# button_brightness_esp32.net
KiCad netlist of a schematic drawn in Altium Designer
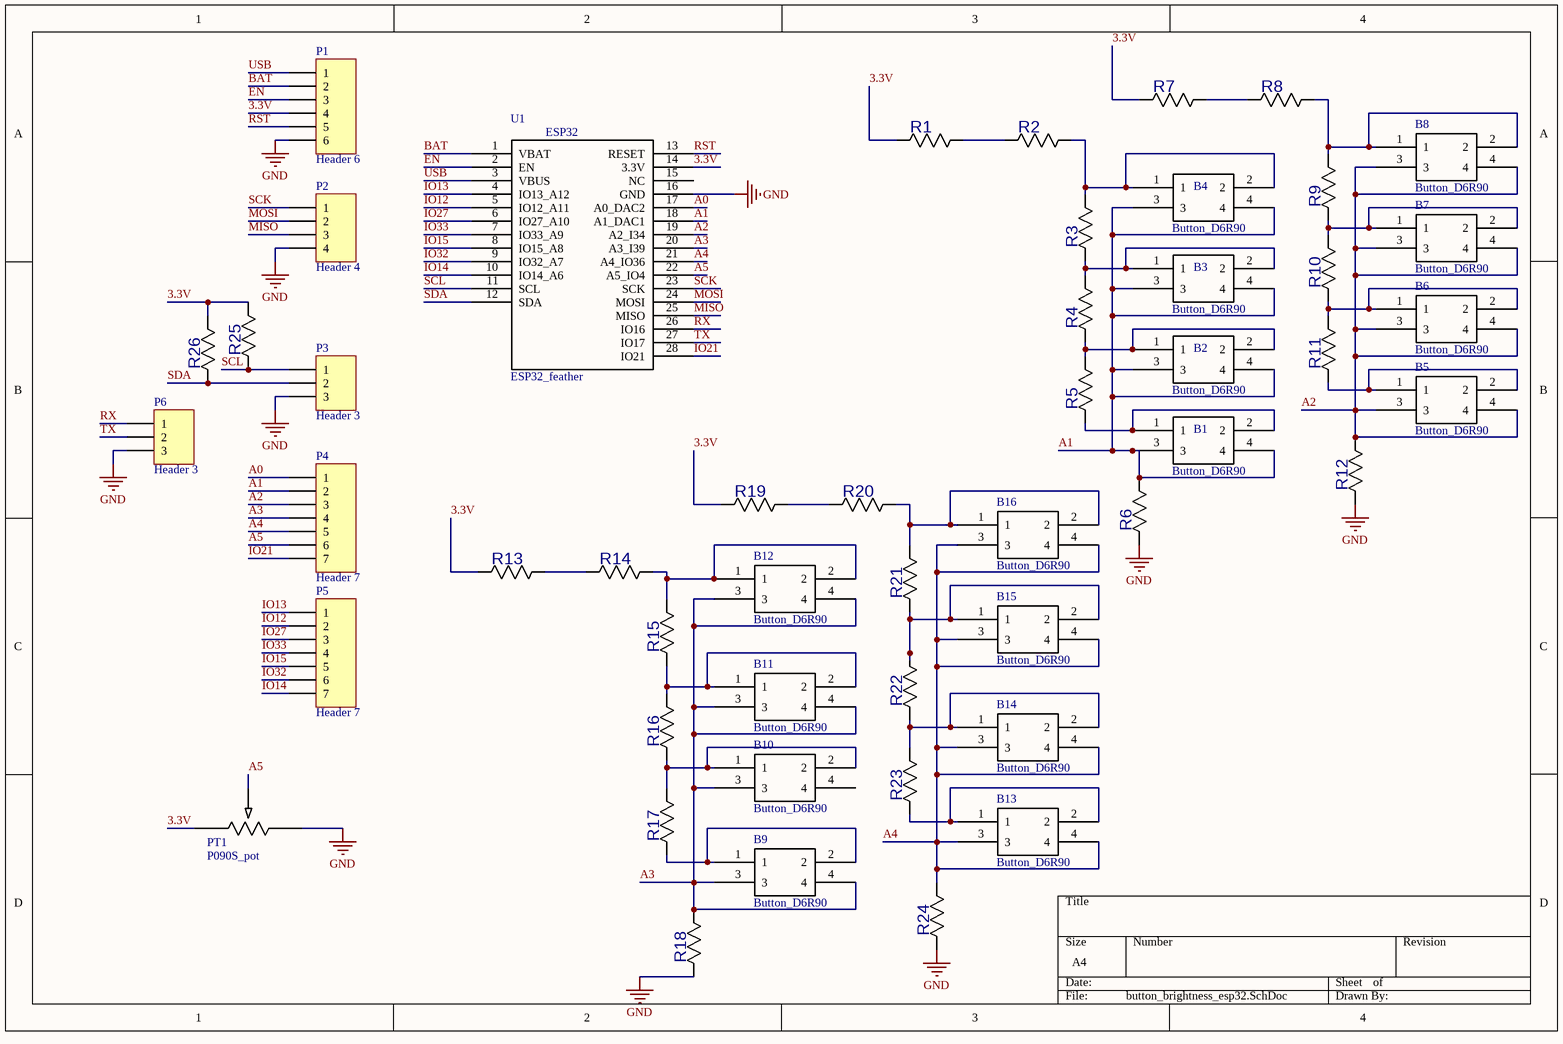
[diagram p0: button_brightness_esp32.SchDoc]

(export (version "E")
  (design (tool "Eeschema 10.0.6"))
  (components
    (comp (ref "B1")
      (value "Button_D6R90")
      (footprint "Button_D6R90")
      (libsource (lib "shematic_lib") (part "Button_D6R90"))
    )
    (comp (ref "B2")
      (value "Button_D6R90")
      (footprint "Button_D6R90")
      (libsource (lib "shematic_lib") (part "Button_D6R90"))
    )
    (comp (ref "B3")
      (value "Button_D6R90")
      (footprint "Button_D6R90")
      (libsource (lib "shematic_lib") (part "Button_D6R90"))
    )
    (comp (ref "B4")
      (value "Button_D6R90")
      (footprint "Button_D6R90")
      (libsource (lib "shematic_lib") (part "Button_D6R90"))
    )
    (comp (ref "B5")
      (value "Button_D6R90")
      (footprint "Button_D6R90")
      (libsource (lib "shematic_lib") (part "Button_D6R90"))
    )
    (comp (ref "B6")
      (value "Button_D6R90")
      (footprint "Button_D6R90")
      (libsource (lib "shematic_lib") (part "Button_D6R90"))
    )
    (comp (ref "B7")
      (value "Button_D6R90")
      (footprint "Button_D6R90")
      (libsource (lib "shematic_lib") (part "Button_D6R90"))
    )
    (comp (ref "B8")
      (value "Button_D6R90")
      (footprint "Button_D6R90")
      (libsource (lib "shematic_lib") (part "Button_D6R90"))
    )
    (comp (ref "B9")
      (value "Button_D6R90")
      (footprint "Button_D6R90")
      (libsource (lib "shematic_lib") (part "Button_D6R90"))
    )
    (comp (ref "B10")
      (value "Button_D6R90")
      (footprint "Button_D6R90")
      (libsource (lib "shematic_lib") (part "Button_D6R90"))
    )
    (comp (ref "B11")
      (value "Button_D6R90")
      (footprint "Button_D6R90")
      (libsource (lib "shematic_lib") (part "Button_D6R90"))
    )
    (comp (ref "B12")
      (value "Button_D6R90")
      (footprint "component_lib:Button_D6R90")
      (libsource (lib "shematic_lib") (part "Button_D6R90"))
    )
    (comp (ref "B13")
      (value "Button_D6R90")
      (footprint "Button_D6R90")
      (libsource (lib "shematic_lib") (part "Button_D6R90"))
    )
    (comp (ref "B14")
      (value "Button_D6R90")
      (footprint "Button_D6R90")
      (libsource (lib "shematic_lib") (part "Button_D6R90"))
    )
    (comp (ref "B15")
      (value "Button_D6R90")
      (footprint "Button_D6R90")
      (libsource (lib "shematic_lib") (part "Button_D6R90"))
    )
    (comp (ref "B16")
      (value "Button_D6R90")
      (footprint "Button_D6R90")
      (libsource (lib "shematic_lib") (part "Button_D6R90"))
    )
    (comp (ref "P1")
      (value "Header 6")
      (footprint "CONN_6")
      (description "Header, 6-Pin")
      (fields (field (name "PUBLISHER") "Altium Limited"))
      (libsource (lib "Miscellaneous Connectors") (part "Header 6"))
    )
    (comp (ref "P2")
      (value "Header 4")
      (footprint "CONN_4")
      (description "Header, 4-Pin")
      (fields (field (name "PUBLISHER") "Altium Limited"))
      (libsource (lib "Miscellaneous Connectors") (part "Header 4"))
    )
    (comp (ref "P3")
      (value "Header 3")
      (footprint "CONN_3")
      (description "Header, 3-Pin")
      (fields (field (name "PUBLISHER") "Altium Limited"))
      (libsource (lib "Miscellaneous Connectors") (part "Header 3"))
    )
    (comp (ref "P4")
      (value "Header 7")
      (footprint "CONN_7")
      (description "Header, 7-Pin")
      (fields (field (name "PUBLISHER") "Altium Limited"))
      (libsource (lib "Miscellaneous Connectors") (part "Header 7"))
    )
    (comp (ref "P5")
      (value "Header 7")
      (footprint "CONN_7")
      (description "Header, 7-Pin")
      (fields (field (name "PUBLISHER") "Altium Limited"))
      (libsource (lib "Miscellaneous Connectors") (part "Header 7"))
    )
    (comp (ref "P6")
      (value "Header 3")
      (footprint "CONN_3")
      (description "Header, 3-Pin")
      (fields (field (name "PUBLISHER") "Altium Limited"))
      (libsource (lib "Miscellaneous Connectors") (part "Header 3"))
    )
    (comp (ref "PT1")
      (value "P090S_pot")
      (footprint "P090S_pot")
      (libsource (lib "shematic_lib") (part "P090S_pot"))
    )
    (comp (ref "R1")
      (value "ERJ-6GEYJ471V")
      (footprint "component_lib:RES_0804_panasonic")
      (libsource (lib "shematic_lib") (part "ERJ-6GEYJ471V"))
    )
    (comp (ref "R2")
      (value "ERJ-6GEYJ471V")
      (footprint "component_lib:RES_0804_panasonic")
      (libsource (lib "shematic_lib") (part "ERJ-6GEYJ471V"))
    )
    (comp (ref "R3")
      (value "ERJ-6GEYJ471V")
      (footprint "component_lib:RES_0804_panasonic")
      (libsource (lib "shematic_lib") (part "ERJ-6GEYJ471V"))
    )
    (comp (ref "R4")
      (value "ERJ-6GEYJ471V")
      (footprint "component_lib:RES_0804_panasonic")
      (libsource (lib "shematic_lib") (part "ERJ-6GEYJ471V"))
    )
    (comp (ref "R5")
      (value "ERJ-6GEYJ471V")
      (footprint "component_lib:RES_0804_panasonic")
      (libsource (lib "shematic_lib") (part "ERJ-6GEYJ471V"))
    )
    (comp (ref "R6")
      (value "ERJ-6GEYJ471V")
      (footprint "component_lib:RES_0804_panasonic")
      (libsource (lib "shematic_lib") (part "ERJ-6GEYJ471V"))
    )
    (comp (ref "R7")
      (value "ERJ-6GEYJ471V")
      (footprint "component_lib:RES_0804_panasonic")
      (libsource (lib "shematic_lib") (part "ERJ-6GEYJ471V"))
    )
    (comp (ref "R8")
      (value "ERJ-6GEYJ471V")
      (footprint "component_lib:RES_0804_panasonic")
      (libsource (lib "shematic_lib") (part "ERJ-6GEYJ471V"))
    )
    (comp (ref "R9")
      (value "ERJ-6GEYJ471V")
      (footprint "component_lib:RES_0804_panasonic")
      (libsource (lib "shematic_lib") (part "ERJ-6GEYJ471V"))
    )
    (comp (ref "R10")
      (value "ERJ-6GEYJ471V")
      (footprint "component_lib:RES_0804_panasonic")
      (libsource (lib "shematic_lib") (part "ERJ-6GEYJ471V"))
    )
    (comp (ref "R11")
      (value "ERJ-6GEYJ471V")
      (footprint "component_lib:RES_0804_panasonic")
      (libsource (lib "shematic_lib") (part "ERJ-6GEYJ471V"))
    )
    (comp (ref "R12")
      (value "ERJ-6GEYJ471V")
      (footprint "component_lib:RES_0804_panasonic")
      (libsource (lib "shematic_lib") (part "ERJ-6GEYJ471V"))
    )
    (comp (ref "R13")
      (value "ERJ-6GEYJ471V")
      (footprint "component_lib:RES_0804_panasonic")
      (libsource (lib "shematic_lib") (part "ERJ-6GEYJ471V"))
    )
    (comp (ref "R14")
      (value "ERJ-6GEYJ471V")
      (footprint "component_lib:RES_0804_panasonic")
      (libsource (lib "shematic_lib") (part "ERJ-6GEYJ471V"))
    )
    (comp (ref "R15")
      (value "ERJ-6GEYJ471V")
      (footprint "component_lib:RES_0804_panasonic")
      (libsource (lib "shematic_lib") (part "ERJ-6GEYJ471V"))
    )
    (comp (ref "R16")
      (value "ERJ-6GEYJ471V")
      (footprint "component_lib:RES_0804_panasonic")
      (libsource (lib "shematic_lib") (part "ERJ-6GEYJ471V"))
    )
    (comp (ref "R17")
      (value "ERJ-6GEYJ471V")
      (footprint "component_lib:RES_0804_panasonic")
      (libsource (lib "shematic_lib") (part "ERJ-6GEYJ471V"))
    )
    (comp (ref "R18")
      (value "ERJ-6GEYJ471V")
      (footprint "component_lib:RES_0804_panasonic")
      (libsource (lib "shematic_lib") (part "ERJ-6GEYJ471V"))
    )
    (comp (ref "R19")
      (value "ERJ-6GEYJ471V")
      (footprint "component_lib:RES_0804_panasonic")
      (libsource (lib "shematic_lib") (part "ERJ-6GEYJ471V"))
    )
    (comp (ref "R20")
      (value "ERJ-6GEYJ471V")
      (footprint "component_lib:RES_0804_panasonic")
      (libsource (lib "shematic_lib") (part "ERJ-6GEYJ471V"))
    )
    (comp (ref "R21")
      (value "ERJ-6GEYJ471V")
      (footprint "component_lib:RES_0804_panasonic")
      (libsource (lib "shematic_lib") (part "ERJ-6GEYJ471V"))
    )
    (comp (ref "R22")
      (value "ERJ-6GEYJ471V")
      (footprint "component_lib:RES_0804_panasonic")
      (libsource (lib "shematic_lib") (part "ERJ-6GEYJ471V"))
    )
    (comp (ref "R23")
      (value "ERJ-6GEYJ471V")
      (footprint "component_lib:RES_0804_panasonic")
      (libsource (lib "shematic_lib") (part "ERJ-6GEYJ471V"))
    )
    (comp (ref "R24")
      (value "ERJ-6GEYJ471V")
      (footprint "component_lib:RES_0804_panasonic")
      (libsource (lib "shematic_lib") (part "ERJ-6GEYJ471V"))
    )
    (comp (ref "R25")
      (value "ERJ-6GEYJ471V")
      (footprint "component_lib:RES_0804_panasonic")
      (libsource (lib "shematic_lib") (part "ERJ-6GEYJ471V"))
    )
    (comp (ref "R26")
      (value "ERJ-6GEYJ471V")
      (footprint "component_lib:RES_0804_panasonic")
      (libsource (lib "shematic_lib") (part "ERJ-6GEYJ471V"))
    )
    (comp (ref "U1")
      (value "ESP32_feather")
      (footprint "ESP32_feather")
      (libsource (lib "shematic_lib") (part "ESP32_feather"))
    )
  )
  (nets
    (net (code "1") (name "/3.3V") (class "Default")
      (node (ref "P1") (pin "4") (pinfunction "4_4") (pintype "passive"))
      (node (ref "PT1") (pin "1") (pinfunction "1_1") (pintype "passive"))
      (node (ref "R1") (pin "2") (pinfunction "2_2") (pintype "passive"))
      (node (ref "R13") (pin "2") (pinfunction "2_2") (pintype "passive"))
      (node (ref "R19") (pin "2") (pinfunction "2_2") (pintype "passive"))
      (node (ref "R25") (pin "1") (pinfunction "1_1") (pintype "passive"))
      (node (ref "R26") (pin "1") (pinfunction "1_1") (pintype "passive"))
      (node (ref "R7") (pin "2") (pinfunction "2_2") (pintype "passive"))
      (node (ref "U1") (pin "14") (pinfunction "3.3V_14") (pintype "passive"))
    )
    (net (code "2") (name "/A0") (class "Default")
      (node (ref "P4") (pin "1") (pinfunction "1_1") (pintype "passive"))
      (node (ref "U1") (pin "17") (pinfunction "A0_DAC2_17") (pintype "passive"))
    )
    (net (code "3") (name "/A1") (class "Default")
      (node (ref "B1") (pin "3") (pinfunction "3_3") (pintype "passive"))
      (node (ref "B1") (pin "4") (pinfunction "4_4") (pintype "passive"))
      (node (ref "B2") (pin "3") (pinfunction "3_3") (pintype "passive"))
      (node (ref "B2") (pin "4") (pinfunction "4_4") (pintype "passive"))
      (node (ref "B3") (pin "3") (pinfunction "3_3") (pintype "passive"))
      (node (ref "B3") (pin "4") (pinfunction "4_4") (pintype "passive"))
      (node (ref "B4") (pin "3") (pinfunction "3_3") (pintype "passive"))
      (node (ref "B4") (pin "4") (pinfunction "4_4") (pintype "passive"))
      (node (ref "P4") (pin "2") (pinfunction "2_2") (pintype "passive"))
      (node (ref "R6") (pin "1") (pinfunction "1_1") (pintype "passive"))
      (node (ref "U1") (pin "18") (pinfunction "A1_DAC1_18") (pintype "passive"))
    )
    (net (code "4") (name "/A2") (class "Default")
      (node (ref "B5") (pin "3") (pinfunction "3_3") (pintype "passive"))
      (node (ref "B5") (pin "4") (pinfunction "4_4") (pintype "passive"))
      (node (ref "B6") (pin "3") (pinfunction "3_3") (pintype "passive"))
      (node (ref "B6") (pin "4") (pinfunction "4_4") (pintype "passive"))
      (node (ref "B7") (pin "3") (pinfunction "3_3") (pintype "passive"))
      (node (ref "B7") (pin "4") (pinfunction "4_4") (pintype "passive"))
      (node (ref "B8") (pin "3") (pinfunction "3_3") (pintype "passive"))
      (node (ref "B8") (pin "4") (pinfunction "4_4") (pintype "passive"))
      (node (ref "P4") (pin "3") (pinfunction "3_3") (pintype "passive"))
      (node (ref "R12") (pin "1") (pinfunction "1_1") (pintype "passive"))
      (node (ref "U1") (pin "19") (pinfunction "A2_I34_19") (pintype "passive"))
    )
    (net (code "5") (name "/A3") (class "Default")
      (node (ref "B10") (pin "3") (pinfunction "3_3") (pintype "passive"))
      (node (ref "B11") (pin "3") (pinfunction "3_3") (pintype "passive"))
      (node (ref "B11") (pin "4") (pinfunction "4_4") (pintype "passive"))
      (node (ref "B12") (pin "3") (pinfunction "3_3") (pintype "passive"))
      (node (ref "B12") (pin "4") (pinfunction "4_4") (pintype "passive"))
      (node (ref "B9") (pin "3") (pinfunction "3_3") (pintype "passive"))
      (node (ref "B9") (pin "4") (pinfunction "4_4") (pintype "passive"))
      (node (ref "P4") (pin "4") (pinfunction "4_4") (pintype "passive"))
      (node (ref "R18") (pin "1") (pinfunction "1_1") (pintype "passive"))
      (node (ref "U1") (pin "20") (pinfunction "A3_I39_20") (pintype "passive"))
    )
    (net (code "6") (name "/A4") (class "Default")
      (node (ref "B13") (pin "3") (pinfunction "3_3") (pintype "passive"))
      (node (ref "B13") (pin "4") (pinfunction "4_4") (pintype "passive"))
      (node (ref "B14") (pin "3") (pinfunction "3_3") (pintype "passive"))
      (node (ref "B14") (pin "4") (pinfunction "4_4") (pintype "passive"))
      (node (ref "B15") (pin "3") (pinfunction "3_3") (pintype "passive"))
      (node (ref "B15") (pin "4") (pinfunction "4_4") (pintype "passive"))
      (node (ref "B16") (pin "3") (pinfunction "3_3") (pintype "passive"))
      (node (ref "B16") (pin "4") (pinfunction "4_4") (pintype "passive"))
      (node (ref "P4") (pin "5") (pinfunction "5_5") (pintype "passive"))
      (node (ref "R24") (pin "1") (pinfunction "1_1") (pintype "passive"))
      (node (ref "U1") (pin "21") (pinfunction "A4_IO36_21") (pintype "passive"))
    )
    (net (code "7") (name "/A5") (class "Default")
      (node (ref "P4") (pin "6") (pinfunction "6_6") (pintype "passive"))
      (node (ref "PT1") (pin "2") (pinfunction "2_2") (pintype "passive"))
      (node (ref "U1") (pin "22") (pinfunction "A5_IO4_22") (pintype "passive"))
    )
    (net (code "8") (name "/BAT") (class "Default")
      (node (ref "P1") (pin "2") (pinfunction "2_2") (pintype "passive"))
      (node (ref "U1") (pin "1") (pinfunction "VBAT_1") (pintype "power_in"))
    )
    (net (code "9") (name "/EN") (class "Default")
      (node (ref "P1") (pin "3") (pinfunction "3_3") (pintype "passive"))
      (node (ref "U1") (pin "2") (pinfunction "EN_2") (pintype "passive"))
    )
    (net (code "10") (name "/IO12") (class "Default")
      (node (ref "P5") (pin "2") (pinfunction "2_2") (pintype "passive"))
      (node (ref "U1") (pin "5") (pinfunction "IO12_A11_5") (pintype "passive"))
    )
    (net (code "11") (name "/IO13") (class "Default")
      (node (ref "P5") (pin "1") (pinfunction "1_1") (pintype "passive"))
      (node (ref "U1") (pin "4") (pinfunction "IO13_A12_4") (pintype "passive"))
    )
    (net (code "12") (name "/IO14") (class "Default")
      (node (ref "P5") (pin "7") (pinfunction "7_7") (pintype "passive"))
      (node (ref "U1") (pin "10") (pinfunction "IO14_A6_10") (pintype "passive"))
    )
    (net (code "13") (name "/IO15") (class "Default")
      (node (ref "P5") (pin "5") (pinfunction "5_5") (pintype "passive"))
      (node (ref "U1") (pin "8") (pinfunction "IO15_A8_8") (pintype "passive"))
    )
    (net (code "14") (name "/IO21") (class "Default")
      (node (ref "P4") (pin "7") (pinfunction "7_7") (pintype "passive"))
      (node (ref "U1") (pin "28") (pinfunction "IO21_28") (pintype "passive"))
    )
    (net (code "15") (name "/IO27") (class "Default")
      (node (ref "P5") (pin "3") (pinfunction "3_3") (pintype "passive"))
      (node (ref "U1") (pin "6") (pinfunction "IO27_A10_6") (pintype "passive"))
    )
    (net (code "16") (name "/IO32") (class "Default")
      (node (ref "P5") (pin "6") (pinfunction "6_6") (pintype "passive"))
      (node (ref "U1") (pin "9") (pinfunction "IO32_A7_9") (pintype "passive"))
    )
    (net (code "17") (name "/IO33") (class "Default")
      (node (ref "P5") (pin "4") (pinfunction "4_4") (pintype "passive"))
      (node (ref "U1") (pin "7") (pinfunction "IO33_A9_7") (pintype "passive"))
    )
    (net (code "18") (name "/MISO") (class "Default")
      (node (ref "P2") (pin "3") (pinfunction "3_3") (pintype "passive"))
      (node (ref "U1") (pin "25") (pinfunction "MISO_25") (pintype "passive"))
    )
    (net (code "19") (name "/MOSI") (class "Default")
      (node (ref "P2") (pin "2") (pinfunction "2_2") (pintype "passive"))
      (node (ref "U1") (pin "24") (pinfunction "MOSI_24") (pintype "passive"))
    )
    (net (code "20") (name "/RST") (class "Default")
      (node (ref "P1") (pin "5") (pinfunction "5_5") (pintype "passive"))
      (node (ref "U1") (pin "13") (pinfunction "RESET_13") (pintype "passive"))
    )
    (net (code "21") (name "/RX") (class "Default")
      (node (ref "P6") (pin "1") (pinfunction "1_1") (pintype "passive"))
      (node (ref "U1") (pin "26") (pinfunction "IO16_26") (pintype "passive"))
    )
    (net (code "22") (name "/SCK") (class "Default")
      (node (ref "P2") (pin "1") (pinfunction "1_1") (pintype "passive"))
      (node (ref "U1") (pin "23") (pinfunction "SCK_23") (pintype "passive"))
    )
    (net (code "23") (name "/SCL") (class "Default")
      (node (ref "P3") (pin "1") (pinfunction "1_1") (pintype "passive"))
      (node (ref "R25") (pin "2") (pinfunction "2_2") (pintype "passive"))
      (node (ref "U1") (pin "11") (pinfunction "SCL_11") (pintype "passive"))
    )
    (net (code "24") (name "/SDA") (class "Default")
      (node (ref "P3") (pin "2") (pinfunction "2_2") (pintype "passive"))
      (node (ref "R26") (pin "2") (pinfunction "2_2") (pintype "passive"))
      (node (ref "U1") (pin "12") (pinfunction "SDA_12") (pintype "passive"))
    )
    (net (code "25") (name "/TX") (class "Default")
      (node (ref "P6") (pin "2") (pinfunction "2_2") (pintype "passive"))
      (node (ref "U1") (pin "27") (pinfunction "IO17_27") (pintype "passive"))
    )
    (net (code "26") (name "/USB") (class "Default")
      (node (ref "P1") (pin "1") (pinfunction "1_1") (pintype "passive"))
      (node (ref "U1") (pin "3") (pinfunction "VBUS_3") (pintype "passive"))
    )
    (net (code "27") (name "GND") (class "Default")
      (node (ref "P1") (pin "6") (pinfunction "6_6") (pintype "passive"))
      (node (ref "P2") (pin "4") (pinfunction "4_4") (pintype "passive"))
      (node (ref "P3") (pin "3") (pinfunction "3_3") (pintype "passive"))
      (node (ref "P6") (pin "3") (pinfunction "3_3") (pintype "passive"))
      (node (ref "PT1") (pin "3") (pinfunction "3_3") (pintype "passive"))
      (node (ref "R12") (pin "2") (pinfunction "2_2") (pintype "passive"))
      (node (ref "R18") (pin "2") (pinfunction "2_2") (pintype "passive"))
      (node (ref "R24") (pin "2") (pinfunction "2_2") (pintype "passive"))
      (node (ref "R6") (pin "2") (pinfunction "2_2") (pintype "passive"))
      (node (ref "U1") (pin "16") (pinfunction "GND_16") (pintype "passive"))
    )
    (net (code "28") (name "Net-(B1-Pad1)") (class "Default")
      (node (ref "B1") (pin "1") (pinfunction "1_1") (pintype "passive"))
      (node (ref "B1") (pin "2") (pinfunction "2_2") (pintype "passive"))
      (node (ref "R5") (pin "2") (pinfunction "2_2") (pintype "passive"))
    )
    (net (code "29") (name "Net-(B2-Pad1)") (class "Default")
      (node (ref "B2") (pin "1") (pinfunction "1_1") (pintype "passive"))
      (node (ref "B2") (pin "2") (pinfunction "2_2") (pintype "passive"))
      (node (ref "R4") (pin "2") (pinfunction "2_2") (pintype "passive"))
      (node (ref "R5") (pin "1") (pinfunction "1_1") (pintype "passive"))
    )
    (net (code "30") (name "Net-(B3-Pad1)") (class "Default")
      (node (ref "B3") (pin "1") (pinfunction "1_1") (pintype "passive"))
      (node (ref "B3") (pin "2") (pinfunction "2_2") (pintype "passive"))
      (node (ref "R3") (pin "2") (pinfunction "2_2") (pintype "passive"))
      (node (ref "R4") (pin "1") (pinfunction "1_1") (pintype "passive"))
    )
    (net (code "31") (name "Net-(B4-Pad1)") (class "Default")
      (node (ref "B4") (pin "1") (pinfunction "1_1") (pintype "passive"))
      (node (ref "B4") (pin "2") (pinfunction "2_2") (pintype "passive"))
      (node (ref "R2") (pin "1") (pinfunction "1_1") (pintype "passive"))
      (node (ref "R3") (pin "1") (pinfunction "1_1") (pintype "passive"))
    )
    (net (code "32") (name "Net-(B5-Pad1)") (class "Default")
      (node (ref "B5") (pin "1") (pinfunction "1_1") (pintype "passive"))
      (node (ref "B5") (pin "2") (pinfunction "2_2") (pintype "passive"))
      (node (ref "R11") (pin "2") (pinfunction "2_2") (pintype "passive"))
    )
    (net (code "33") (name "Net-(B6-Pad1)") (class "Default")
      (node (ref "B6") (pin "1") (pinfunction "1_1") (pintype "passive"))
      (node (ref "B6") (pin "2") (pinfunction "2_2") (pintype "passive"))
      (node (ref "R10") (pin "2") (pinfunction "2_2") (pintype "passive"))
      (node (ref "R11") (pin "1") (pinfunction "1_1") (pintype "passive"))
    )
    (net (code "34") (name "Net-(B7-Pad1)") (class "Default")
      (node (ref "B7") (pin "1") (pinfunction "1_1") (pintype "passive"))
      (node (ref "B7") (pin "2") (pinfunction "2_2") (pintype "passive"))
      (node (ref "R10") (pin "1") (pinfunction "1_1") (pintype "passive"))
      (node (ref "R9") (pin "2") (pinfunction "2_2") (pintype "passive"))
    )
    (net (code "35") (name "Net-(B8-Pad1)") (class "Default")
      (node (ref "B8") (pin "1") (pinfunction "1_1") (pintype "passive"))
      (node (ref "B8") (pin "2") (pinfunction "2_2") (pintype "passive"))
      (node (ref "R8") (pin "1") (pinfunction "1_1") (pintype "passive"))
      (node (ref "R9") (pin "1") (pinfunction "1_1") (pintype "passive"))
    )
    (net (code "36") (name "Net-(B9-Pad1)") (class "Default")
      (node (ref "B9") (pin "1") (pinfunction "1_1") (pintype "passive"))
      (node (ref "B9") (pin "2") (pinfunction "2_2") (pintype "passive"))
      (node (ref "R17") (pin "2") (pinfunction "2_2") (pintype "passive"))
    )
    (net (code "37") (name "Net-(B10-Pad1)") (class "Default")
      (node (ref "B10") (pin "1") (pinfunction "1_1") (pintype "passive"))
      (node (ref "B10") (pin "2") (pinfunction "2_2") (pintype "passive"))
      (node (ref "R16") (pin "2") (pinfunction "2_2") (pintype "passive"))
      (node (ref "R17") (pin "1") (pinfunction "1_1") (pintype "passive"))
    )
    (net (code "38") (name "Net-(B11-Pad1)") (class "Default")
      (node (ref "B11") (pin "1") (pinfunction "1_1") (pintype "passive"))
      (node (ref "B11") (pin "2") (pinfunction "2_2") (pintype "passive"))
      (node (ref "R15") (pin "2") (pinfunction "2_2") (pintype "passive"))
      (node (ref "R16") (pin "1") (pinfunction "1_1") (pintype "passive"))
    )
    (net (code "39") (name "Net-(B12-Pad1)") (class "Default")
      (node (ref "B12") (pin "1") (pinfunction "1_1") (pintype "passive"))
      (node (ref "B12") (pin "2") (pinfunction "2_2") (pintype "passive"))
      (node (ref "R14") (pin "1") (pinfunction "1_1") (pintype "passive"))
      (node (ref "R15") (pin "1") (pinfunction "1_1") (pintype "passive"))
    )
    (net (code "40") (name "Net-(B13-Pad1)") (class "Default")
      (node (ref "B13") (pin "1") (pinfunction "1_1") (pintype "passive"))
      (node (ref "B13") (pin "2") (pinfunction "2_2") (pintype "passive"))
      (node (ref "R23") (pin "2") (pinfunction "2_2") (pintype "passive"))
    )
    (net (code "41") (name "Net-(B14-Pad1)") (class "Default")
      (node (ref "B14") (pin "1") (pinfunction "1_1") (pintype "passive"))
      (node (ref "B14") (pin "2") (pinfunction "2_2") (pintype "passive"))
      (node (ref "R22") (pin "2") (pinfunction "2_2") (pintype "passive"))
      (node (ref "R23") (pin "1") (pinfunction "1_1") (pintype "passive"))
    )
    (net (code "42") (name "Net-(B15-Pad1)") (class "Default")
      (node (ref "B15") (pin "1") (pinfunction "1_1") (pintype "passive"))
      (node (ref "B15") (pin "2") (pinfunction "2_2") (pintype "passive"))
      (node (ref "R21") (pin "2") (pinfunction "2_2") (pintype "passive"))
      (node (ref "R22") (pin "1") (pinfunction "1_1") (pintype "passive"))
    )
    (net (code "43") (name "Net-(B16-Pad1)") (class "Default")
      (node (ref "B16") (pin "1") (pinfunction "1_1") (pintype "passive"))
      (node (ref "B16") (pin "2") (pinfunction "2_2") (pintype "passive"))
      (node (ref "R20") (pin "1") (pinfunction "1_1") (pintype "passive"))
      (node (ref "R21") (pin "1") (pinfunction "1_1") (pintype "passive"))
    )
    (net (code "44") (name "Net-(R1-Pad1)") (class "Default")
      (node (ref "R1") (pin "1") (pinfunction "1_1") (pintype "passive"))
      (node (ref "R2") (pin "2") (pinfunction "2_2") (pintype "passive"))
    )
    (net (code "45") (name "Net-(R7-Pad1)") (class "Default")
      (node (ref "R7") (pin "1") (pinfunction "1_1") (pintype "passive"))
      (node (ref "R8") (pin "2") (pinfunction "2_2") (pintype "passive"))
    )
    (net (code "46") (name "Net-(R13-Pad1)") (class "Default")
      (node (ref "R13") (pin "1") (pinfunction "1_1") (pintype "passive"))
      (node (ref "R14") (pin "2") (pinfunction "2_2") (pintype "passive"))
    )
    (net (code "47") (name "Net-(R19-Pad1)") (class "Default")
      (node (ref "R19") (pin "1") (pinfunction "1_1") (pintype "passive"))
      (node (ref "R20") (pin "2") (pinfunction "2_2") (pintype "passive"))
    )
    (net (code "48") (name "unconnected-(B10-Pad4)") (class "Default")
      (node (ref "B10") (pin "4") (pinfunction "4_4") (pintype "passive"))
    )
    (net (code "49") (name "unconnected-(U1-NC-Pad15)") (class "Default")
      (node (ref "U1") (pin "15") (pinfunction "NC_15") (pintype "passive"))
    )
  )
)
